# schematic.net
KiCad netlist of a schematic drawn in Altium Designer
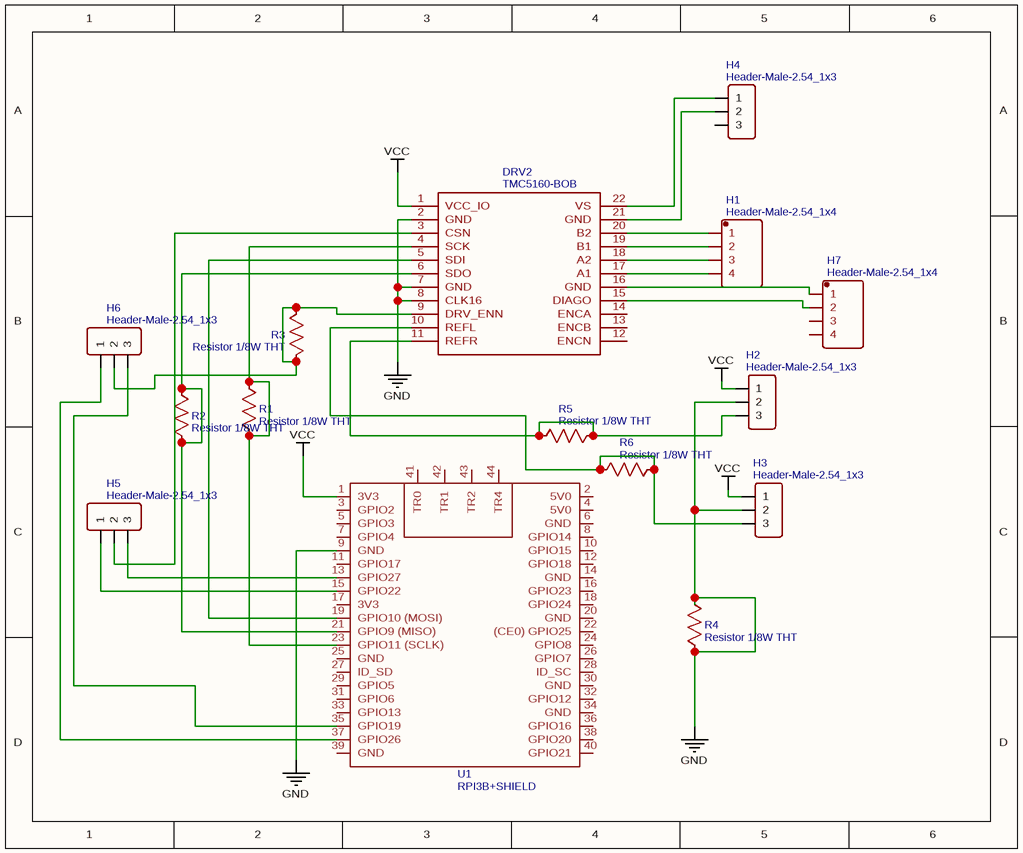
[diagram p0: schematic.schdoc]

(export (version "E")
  (design (tool "Eeschema 10.0.6"))
  (components
    (comp (ref "DRV2")
      (value "TMC5160-BOB")
      (fields (field (name "CONTRIBUTOR") "alexackerman96"))
      (libsource (lib "altium-import") (part "root_0_TMC5160-BOB_"))
    )
    (comp (ref "H1")
      (value "Header-Male-2.54_1x4")
      (fields
        (field (name "BOM_MANUFACTURER PART") "210S-1*4P L=11.6MMGold-plated black")
        (field (name "BOM_SUPPLIER PART") "C124378")
        (field (name "CONTRIBUTOR") "LCSC")
      )
      (libsource (lib "altium-import") (part "root_0_Header-Male-2.54_1x4_"))
    )
    (comp (ref "H2")
      (value "Header-Male-2.54_1x3")
      (fields
        (field (name "BOM_MANUFACTURER PART") "Header2.54mm 1*3P")
        (field (name "BOM_SUPPLIER PART") "C49257")
      )
      (libsource (lib "altium-import") (part "root_0_Header-Male-2.54_1x3_"))
    )
    (comp (ref "H3")
      (value "Header-Male-2.54_1x3")
      (fields
        (field (name "BOM_MANUFACTURER PART") "Header2.54mm 1*3P")
        (field (name "BOM_SUPPLIER PART") "C49257")
      )
      (libsource (lib "altium-import") (part "root_0_Header-Male-2.54_1x3_"))
    )
    (comp (ref "H4")
      (value "Header-Male-2.54_1x3")
      (fields
        (field (name "BOM_MANUFACTURER PART") "Header2.54mm 1*3P")
        (field (name "BOM_SUPPLIER PART") "C49257")
      )
      (libsource (lib "altium-import") (part "root_0_Header-Male-2.54_1x3_"))
    )
    (comp (ref "H5")
      (value "Header-Male-2.54_1x3")
      (fields
        (field (name "BOM_MANUFACTURER PART") "Header2.54mm 1*3P")
        (field (name "BOM_SUPPLIER PART") "C49257")
      )
      (libsource (lib "altium-import") (part "root_1_Header-Male-2.54_1x3_"))
    )
    (comp (ref "H6")
      (value "Header-Male-2.54_1x3")
      (fields
        (field (name "BOM_MANUFACTURER PART") "Header2.54mm 1*3P")
        (field (name "BOM_SUPPLIER PART") "C49257")
      )
      (libsource (lib "altium-import") (part "root_1_Header-Male-2.54_1x3_"))
    )
    (comp (ref "H7")
      (value "Header-Male-2.54_1x4")
      (fields
        (field (name "BOM_MANUFACTURER PART") "210S-1*4P L=11.6MMGold-plated black")
        (field (name "BOM_SUPPLIER PART") "C124378")
        (field (name "CONTRIBUTOR") "LCSC")
      )
      (libsource (lib "altium-import") (part "root_0_Header-Male-2.54_1x4_"))
    )
    (comp (ref "R1")
      (value "Resistor 1/8W THT")
      (fields (field (name "BOM_MANUFACTURER PART") "Generic") (field (name "CONTRIBUTOR") "tyvogelpohl"))
      (libsource (lib "") (part "root_1_Resistor 1/8W THT__1"))
    )
    (comp (ref "R2")
      (value "Resistor 1/8W THT")
      (fields (field (name "BOM_MANUFACTURER PART") "Generic") (field (name "CONTRIBUTOR") "tyvogelpohl"))
      (libsource (lib "") (part "root_1_Resistor 1/8W THT__1"))
    )
    (comp (ref "R3")
      (value "Resistor 1/8W THT")
      (fields (field (name "BOM_MANUFACTURER PART") "Generic") (field (name "CONTRIBUTOR") "tyvogelpohl"))
      (libsource (lib "altium-import") (part "root_1_Resistor 1/8W THT_"))
    )
    (comp (ref "R4")
      (value "Resistor 1/8W THT")
      (fields (field (name "BOM_MANUFACTURER PART") "Generic") (field (name "CONTRIBUTOR") "tyvogelpohl"))
      (libsource (lib "") (part "root_1_Resistor 1/8W THT__1"))
    )
    (comp (ref "R5")
      (value "Resistor 1/8W THT")
      (fields (field (name "BOM_MANUFACTURER PART") "Generic") (field (name "CONTRIBUTOR") "tyvogelpohl"))
      (libsource (lib "altium-import") (part "root_2_Resistor 1/8W THT_"))
    )
    (comp (ref "R6")
      (value "Resistor 1/8W THT")
      (fields (field (name "BOM_MANUFACTURER PART") "Generic") (field (name "CONTRIBUTOR") "tyvogelpohl"))
      (libsource (lib "altium-import") (part "root_2_Resistor 1/8W THT_"))
    )
    (comp (ref "U1")
      (value "RPI3B+SHIELD")
      (fields (field (name "BOM_MANUFACTURER PART") "RaspberryPi 3") (field (name "CONTRIBUTOR") "gdevries"))
      (libsource (lib "altium-import") (part "root_0_RPI3B+SHIELD_"))
    )
  )
  (nets
    (net (code "1") (name "GND") (class "Default")
      (node (ref "DRV2") (pin "2") (pinfunction "GND_2") (pintype "passive"))
      (node (ref "DRV2") (pin "7") (pinfunction "GND_7") (pintype "passive"))
      (node (ref "DRV2") (pin "8") (pinfunction "CLK16_8") (pintype "passive"))
      (node (ref "H2") (pin "2") (pinfunction "2_2") (pintype "passive"))
      (node (ref "H3") (pin "2") (pinfunction "2_2") (pintype "passive"))
      (node (ref "R4") (pin "1") (pinfunction "1_1") (pintype "passive"))
      (node (ref "R4") (pin "2") (pinfunction "2_2") (pintype "passive"))
      (node (ref "U1") (pin "9") (pinfunction "GND_9") (pintype "passive"))
    )
    (net (code "2") (name "Net-(DRV2-A1)") (class "Default")
      (node (ref "DRV2") (pin "17") (pinfunction "A1_17") (pintype "passive"))
      (node (ref "H1") (pin "4") (pinfunction "4_4") (pintype "passive"))
    )
    (net (code "3") (name "Net-(DRV2-A2)") (class "Default")
      (node (ref "DRV2") (pin "18") (pinfunction "A2_18") (pintype "passive"))
      (node (ref "H1") (pin "3") (pinfunction "3_3") (pintype "passive"))
    )
    (net (code "4") (name "Net-(DRV2-B1)") (class "Default")
      (node (ref "DRV2") (pin "19") (pinfunction "B1_19") (pintype "passive"))
      (node (ref "H1") (pin "2") (pinfunction "2_2") (pintype "passive"))
    )
    (net (code "5") (name "Net-(DRV2-B2)") (class "Default")
      (node (ref "DRV2") (pin "20") (pinfunction "B2_20") (pintype "passive"))
      (node (ref "H1") (pin "1") (pinfunction "1_1") (pintype "passive"))
    )
    (net (code "6") (name "Net-(DRV2-CSN)") (class "Default")
      (node (ref "DRV2") (pin "3") (pinfunction "CSN_3") (pintype "passive"))
      (node (ref "H5") (pin "2") (pinfunction "2_2") (pintype "passive"))
    )
    (net (code "7") (name "Net-(DRV2-DIAGO)") (class "Default")
      (node (ref "DRV2") (pin "15") (pinfunction "DIAGO_15") (pintype "passive"))
      (node (ref "H7") (pin "2") (pinfunction "2_2") (pintype "passive"))
    )
    (net (code "8") (name "Net-(DRV2-DRV_ENN)") (class "Default")
      (node (ref "DRV2") (pin "9") (pinfunction "DRV_ENN_9") (pintype "passive"))
      (node (ref "H6") (pin "2") (pinfunction "2_2") (pintype "passive"))
      (node (ref "R3") (pin "1") (pinfunction "1_1") (pintype "passive"))
      (node (ref "R3") (pin "2") (pinfunction "2_2") (pintype "passive"))
    )
    (net (code "9") (name "Net-(DRV2-GND-Pad16)") (class "Default")
      (node (ref "DRV2") (pin "16") (pinfunction "GND_16") (pintype "passive"))
      (node (ref "H7") (pin "1") (pinfunction "1_1") (pintype "passive"))
    )
    (net (code "10") (name "Net-(DRV2-GND-Pad21)") (class "Default")
      (node (ref "DRV2") (pin "21") (pinfunction "GND_21") (pintype "passive"))
      (node (ref "H4") (pin "2") (pinfunction "2_2") (pintype "passive"))
    )
    (net (code "11") (name "Net-(DRV2-REFL)") (class "Default")
      (node (ref "DRV2") (pin "10") (pinfunction "REFL_10") (pintype "passive"))
      (node (ref "H3") (pin "3") (pinfunction "3_3") (pintype "passive"))
      (node (ref "R6") (pin "1") (pinfunction "1_1") (pintype "passive"))
      (node (ref "R6") (pin "2") (pinfunction "2_2") (pintype "passive"))
    )
    (net (code "12") (name "Net-(DRV2-REFR)") (class "Default")
      (node (ref "DRV2") (pin "11") (pinfunction "REFR_11") (pintype "passive"))
      (node (ref "H2") (pin "3") (pinfunction "3_3") (pintype "passive"))
      (node (ref "R5") (pin "1") (pinfunction "1_1") (pintype "passive"))
      (node (ref "R5") (pin "2") (pinfunction "2_2") (pintype "passive"))
    )
    (net (code "13") (name "Net-(DRV2-SCK)") (class "Default")
      (node (ref "DRV2") (pin "4") (pinfunction "SCK_4") (pintype "passive"))
      (node (ref "R1") (pin "1") (pinfunction "1_1") (pintype "passive"))
      (node (ref "R1") (pin "2") (pinfunction "2_2") (pintype "passive"))
      (node (ref "U1") (pin "23") (pinfunction "GPIO11_(SCLK)_23") (pintype "passive"))
    )
    (net (code "14") (name "Net-(DRV2-SDI)") (class "Default")
      (node (ref "DRV2") (pin "5") (pinfunction "SDI_5") (pintype "passive"))
      (node (ref "U1") (pin "19") (pinfunction "GPIO10_(MOSI)_19") (pintype "passive"))
    )
    (net (code "15") (name "Net-(DRV2-SDO)") (class "Default")
      (node (ref "DRV2") (pin "6") (pinfunction "SDO_6") (pintype "passive"))
      (node (ref "R2") (pin "1") (pinfunction "1_1") (pintype "passive"))
      (node (ref "R2") (pin "2") (pinfunction "2_2") (pintype "passive"))
      (node (ref "U1") (pin "21") (pinfunction "GPIO9_(MISO)_21") (pintype "passive"))
    )
    (net (code "16") (name "Net-(DRV2-VS)") (class "Default")
      (node (ref "DRV2") (pin "22") (pinfunction "VS_22") (pintype "passive"))
      (node (ref "H4") (pin "1") (pinfunction "1_1") (pintype "passive"))
    )
    (net (code "17") (name "Net-(U1-GPIO19)") (class "Default")
      (node (ref "H6") (pin "3") (pinfunction "3_3") (pintype "passive"))
      (node (ref "U1") (pin "35") (pinfunction "GPIO19_35") (pintype "passive"))
    )
    (net (code "18") (name "Net-(U1-GPIO22)") (class "Default")
      (node (ref "H5") (pin "1") (pinfunction "1_1") (pintype "passive"))
      (node (ref "U1") (pin "15") (pinfunction "GPIO22_15") (pintype "passive"))
    )
    (net (code "19") (name "Net-(U1-GPIO26)") (class "Default")
      (node (ref "H6") (pin "1") (pinfunction "1_1") (pintype "passive"))
      (node (ref "U1") (pin "37") (pinfunction "GPIO26_37") (pintype "passive"))
    )
    (net (code "20") (name "Net-(U1-GPIO27)") (class "Default")
      (node (ref "H5") (pin "3") (pinfunction "3_3") (pintype "passive"))
      (node (ref "U1") (pin "13") (pinfunction "GPIO27_13") (pintype "passive"))
    )
    (net (code "21") (name "VCC") (class "Default")
      (node (ref "DRV2") (pin "1") (pinfunction "VCC_IO_1") (pintype "passive"))
      (node (ref "H2") (pin "1") (pinfunction "1_1") (pintype "passive"))
      (node (ref "H3") (pin "1") (pinfunction "1_1") (pintype "passive"))
      (node (ref "U1") (pin "1") (pinfunction "3V3_1") (pintype "passive"))
    )
    (net (code "22") (name "unconnected-(DRV2-ENCA-Pad14)") (class "Default")
      (node (ref "DRV2") (pin "14") (pinfunction "ENCA_14") (pintype "passive"))
    )
    (net (code "23") (name "unconnected-(DRV2-ENCB-Pad13)") (class "Default")
      (node (ref "DRV2") (pin "13") (pinfunction "ENCB_13") (pintype "passive"))
    )
    (net (code "24") (name "unconnected-(DRV2-ENCN-Pad12)") (class "Default")
      (node (ref "DRV2") (pin "12") (pinfunction "ENCN_12") (pintype "passive"))
    )
    (net (code "25") (name "unconnected-(H4-Pad3)") (class "Default")
      (node (ref "H4") (pin "3") (pinfunction "3_3") (pintype "passive"))
    )
    (net (code "26") (name "unconnected-(H7-Pad3)") (class "Default")
      (node (ref "H7") (pin "3") (pinfunction "3_3") (pintype "passive"))
    )
    (net (code "27") (name "unconnected-(H7-Pad4)") (class "Default")
      (node (ref "H7") (pin "4") (pinfunction "4_4") (pintype "passive"))
    )
    (net (code "28") (name "unconnected-(U1-(CE0)_GPIO25-Pad22)") (class "Default")
      (node (ref "U1") (pin "22") (pinfunction "(CE0)_GPIO25_22") (pintype "passive"))
    )
    (net (code "29") (name "unconnected-(U1-3V3-Pad17)") (class "Default")
      (node (ref "U1") (pin "17") (pinfunction "3V3_17") (pintype "passive"))
    )
    (net (code "30") (name "unconnected-(U1-5V0-Pad2)") (class "Default")
      (node (ref "U1") (pin "2") (pinfunction "5V0_2") (pintype "passive"))
    )
    (net (code "31") (name "unconnected-(U1-5V0-Pad4)") (class "Default")
      (node (ref "U1") (pin "4") (pinfunction "5V0_4") (pintype "passive"))
    )
    (net (code "32") (name "unconnected-(U1-GND-Pad6)") (class "Default")
      (node (ref "U1") (pin "6") (pinfunction "GND_6") (pintype "passive"))
    )
    (net (code "33") (name "unconnected-(U1-GND-Pad14)") (class "Default")
      (node (ref "U1") (pin "14") (pinfunction "GND_14") (pintype "passive"))
    )
    (net (code "34") (name "unconnected-(U1-GND-Pad20)") (class "Default")
      (node (ref "U1") (pin "20") (pinfunction "GND_20") (pintype "passive"))
    )
    (net (code "35") (name "unconnected-(U1-GND-Pad25)") (class "Default")
      (node (ref "U1") (pin "25") (pinfunction "GND_25") (pintype "passive"))
    )
    (net (code "36") (name "unconnected-(U1-GND-Pad30)") (class "Default")
      (node (ref "U1") (pin "30") (pinfunction "GND_30") (pintype "passive"))
    )
    (net (code "37") (name "unconnected-(U1-GND-Pad34)") (class "Default")
      (node (ref "U1") (pin "34") (pinfunction "GND_34") (pintype "passive"))
    )
    (net (code "38") (name "unconnected-(U1-GND-Pad39)") (class "Default")
      (node (ref "U1") (pin "39") (pinfunction "GND_39") (pintype "passive"))
    )
    (net (code "39") (name "unconnected-(U1-GPIO2-Pad3)") (class "Default")
      (node (ref "U1") (pin "3") (pinfunction "GPIO2_3") (pintype "passive"))
    )
    (net (code "40") (name "unconnected-(U1-GPIO3-Pad5)") (class "Default")
      (node (ref "U1") (pin "5") (pinfunction "GPIO3_5") (pintype "passive"))
    )
    (net (code "41") (name "unconnected-(U1-GPIO4-Pad7)") (class "Default")
      (node (ref "U1") (pin "7") (pinfunction "GPIO4_7") (pintype "passive"))
    )
    (net (code "42") (name "unconnected-(U1-GPIO5-Pad29)") (class "Default")
      (node (ref "U1") (pin "29") (pinfunction "GPIO5_29") (pintype "passive"))
    )
    (net (code "43") (name "unconnected-(U1-GPIO6-Pad31)") (class "Default")
      (node (ref "U1") (pin "31") (pinfunction "GPIO6_31") (pintype "passive"))
    )
    (net (code "44") (name "unconnected-(U1-GPIO7-Pad26)") (class "Default")
      (node (ref "U1") (pin "26") (pinfunction "GPIO7_26") (pintype "passive"))
    )
    (net (code "45") (name "unconnected-(U1-GPIO8-Pad24)") (class "Default")
      (node (ref "U1") (pin "24") (pinfunction "GPIO8_24") (pintype "passive"))
    )
    (net (code "46") (name "unconnected-(U1-GPIO12-Pad32)") (class "Default")
      (node (ref "U1") (pin "32") (pinfunction "GPIO12_32") (pintype "passive"))
    )
    (net (code "47") (name "unconnected-(U1-GPIO13-Pad33)") (class "Default")
      (node (ref "U1") (pin "33") (pinfunction "GPIO13_33") (pintype "passive"))
    )
    (net (code "48") (name "unconnected-(U1-GPIO14-Pad8)") (class "Default")
      (node (ref "U1") (pin "8") (pinfunction "GPIO14_8") (pintype "passive"))
    )
    (net (code "49") (name "unconnected-(U1-GPIO15-Pad10)") (class "Default")
      (node (ref "U1") (pin "10") (pinfunction "GPIO15_10") (pintype "passive"))
    )
    (net (code "50") (name "unconnected-(U1-GPIO16-Pad36)") (class "Default")
      (node (ref "U1") (pin "36") (pinfunction "GPIO16_36") (pintype "passive"))
    )
    (net (code "51") (name "unconnected-(U1-GPIO17-Pad11)") (class "Default")
      (node (ref "U1") (pin "11") (pinfunction "GPIO17_11") (pintype "passive"))
    )
    (net (code "52") (name "unconnected-(U1-GPIO18-Pad12)") (class "Default")
      (node (ref "U1") (pin "12") (pinfunction "GPIO18_12") (pintype "passive"))
    )
    (net (code "53") (name "unconnected-(U1-GPIO20-Pad38)") (class "Default")
      (node (ref "U1") (pin "38") (pinfunction "GPIO20_38") (pintype "passive"))
    )
    (net (code "54") (name "unconnected-(U1-GPIO21-Pad40)") (class "Default")
      (node (ref "U1") (pin "40") (pinfunction "GPIO21_40") (pintype "passive"))
    )
    (net (code "55") (name "unconnected-(U1-GPIO23-Pad16)") (class "Default")
      (node (ref "U1") (pin "16") (pinfunction "GPIO23_16") (pintype "passive"))
    )
    (net (code "56") (name "unconnected-(U1-GPIO24-Pad18)") (class "Default")
      (node (ref "U1") (pin "18") (pinfunction "GPIO24_18") (pintype "passive"))
    )
    (net (code "57") (name "unconnected-(U1-ID_SC-Pad28)") (class "Default")
      (node (ref "U1") (pin "28") (pinfunction "ID_SC_28") (pintype "passive"))
    )
    (net (code "58") (name "unconnected-(U1-ID_SD-Pad27)") (class "Default")
      (node (ref "U1") (pin "27") (pinfunction "ID_SD_27") (pintype "passive"))
    )
    (net (code "59") (name "unconnected-(U1-TR0-Pad41)") (class "Default")
      (node (ref "U1") (pin "41") (pinfunction "TR0_41") (pintype "passive"))
    )
    (net (code "60") (name "unconnected-(U1-TR1-Pad42)") (class "Default")
      (node (ref "U1") (pin "42") (pinfunction "TR1_42") (pintype "passive"))
    )
    (net (code "61") (name "unconnected-(U1-TR2-Pad43)") (class "Default")
      (node (ref "U1") (pin "43") (pinfunction "TR2_43") (pintype "passive"))
    )
    (net (code "62") (name "unconnected-(U1-TR4-Pad44)") (class "Default")
      (node (ref "U1") (pin "44") (pinfunction "TR4_44") (pintype "passive"))
    )
  )
)
